# Hydrophones_0_1in_Adapter.net
KiCad netlist of a schematic drawn in Altium Designer
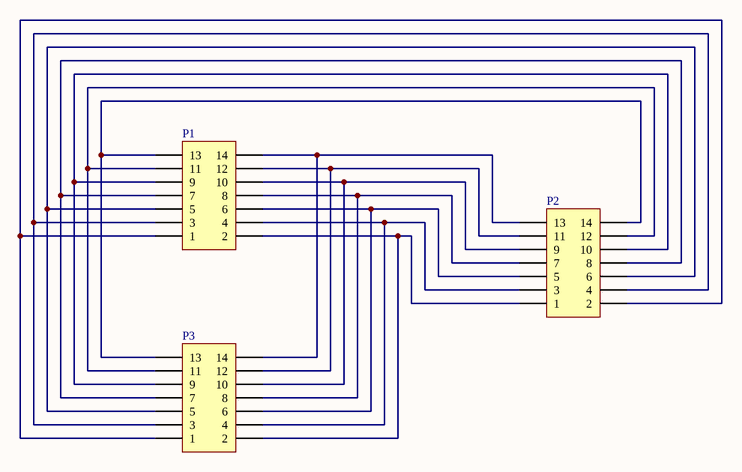
[diagram p0: Hydrophones_0.1in_Adapter.SchDoc]

(export (version "E")
  (design (tool "Eeschema 10.0.6"))
  (components
    (comp (ref "P1")
      (value "Header 7X2")
      (footprint "FTSH-107-01-F-DV")
      (description "Header, 7-Pin, Dual row")
      (fields (field (name "PUBLISHER") "Altium Limited"))
      (libsource (lib "Miscellaneous Connectors") (part "Header 7X2"))
    )
    (comp (ref "P2")
      (value "Header 7X2")
      (footprint "HDR2X7")
      (description "Header, 7-Pin, Dual row")
      (fields (field (name "PUBLISHER") "Altium Limited"))
      (libsource (lib "Miscellaneous Connectors") (part "Header 7X2"))
    )
    (comp (ref "P3")
      (value "Header 7X2")
      (footprint "FTSH-107-01-F-DV")
      (description "Header, 7-Pin, Dual row")
      (fields (field (name "PUBLISHER") "Altium Limited"))
      (libsource (lib "Miscellaneous Connectors") (part "Header 7X2"))
    )
  )
  (nets
    (net (code "1") (name "Net-(P1-Pad1)") (class "Default")
      (node (ref "P1") (pin "1") (pinfunction "1_1") (pintype "passive"))
      (node (ref "P2") (pin "2") (pinfunction "2_2") (pintype "passive"))
      (node (ref "P3") (pin "1") (pinfunction "1_1") (pintype "passive"))
    )
    (net (code "2") (name "Net-(P1-Pad2)") (class "Default")
      (node (ref "P1") (pin "2") (pinfunction "2_2") (pintype "passive"))
      (node (ref "P2") (pin "1") (pinfunction "1_1") (pintype "passive"))
      (node (ref "P3") (pin "2") (pinfunction "2_2") (pintype "passive"))
    )
    (net (code "3") (name "Net-(P1-Pad3)") (class "Default")
      (node (ref "P1") (pin "3") (pinfunction "3_3") (pintype "passive"))
      (node (ref "P2") (pin "4") (pinfunction "4_4") (pintype "passive"))
      (node (ref "P3") (pin "3") (pinfunction "3_3") (pintype "passive"))
    )
    (net (code "4") (name "Net-(P1-Pad4)") (class "Default")
      (node (ref "P1") (pin "4") (pinfunction "4_4") (pintype "passive"))
      (node (ref "P2") (pin "3") (pinfunction "3_3") (pintype "passive"))
      (node (ref "P3") (pin "4") (pinfunction "4_4") (pintype "passive"))
    )
    (net (code "5") (name "Net-(P1-Pad5)") (class "Default")
      (node (ref "P1") (pin "5") (pinfunction "5_5") (pintype "passive"))
      (node (ref "P2") (pin "6") (pinfunction "6_6") (pintype "passive"))
      (node (ref "P3") (pin "5") (pinfunction "5_5") (pintype "passive"))
    )
    (net (code "6") (name "Net-(P1-Pad6)") (class "Default")
      (node (ref "P1") (pin "6") (pinfunction "6_6") (pintype "passive"))
      (node (ref "P2") (pin "5") (pinfunction "5_5") (pintype "passive"))
      (node (ref "P3") (pin "6") (pinfunction "6_6") (pintype "passive"))
    )
    (net (code "7") (name "Net-(P1-Pad7)") (class "Default")
      (node (ref "P1") (pin "7") (pinfunction "7_7") (pintype "passive"))
      (node (ref "P2") (pin "8") (pinfunction "8_8") (pintype "passive"))
      (node (ref "P3") (pin "7") (pinfunction "7_7") (pintype "passive"))
    )
    (net (code "8") (name "Net-(P1-Pad8)") (class "Default")
      (node (ref "P1") (pin "8") (pinfunction "8_8") (pintype "passive"))
      (node (ref "P2") (pin "7") (pinfunction "7_7") (pintype "passive"))
      (node (ref "P3") (pin "8") (pinfunction "8_8") (pintype "passive"))
    )
    (net (code "9") (name "Net-(P1-Pad9)") (class "Default")
      (node (ref "P1") (pin "9") (pinfunction "9_9") (pintype "passive"))
      (node (ref "P2") (pin "10") (pinfunction "10_10") (pintype "passive"))
      (node (ref "P3") (pin "9") (pinfunction "9_9") (pintype "passive"))
    )
    (net (code "10") (name "Net-(P1-Pad10)") (class "Default")
      (node (ref "P1") (pin "10") (pinfunction "10_10") (pintype "passive"))
      (node (ref "P2") (pin "9") (pinfunction "9_9") (pintype "passive"))
      (node (ref "P3") (pin "10") (pinfunction "10_10") (pintype "passive"))
    )
    (net (code "11") (name "Net-(P1-Pad11)") (class "Default")
      (node (ref "P1") (pin "11") (pinfunction "11_11") (pintype "passive"))
      (node (ref "P2") (pin "12") (pinfunction "12_12") (pintype "passive"))
      (node (ref "P3") (pin "11") (pinfunction "11_11") (pintype "passive"))
    )
    (net (code "12") (name "Net-(P1-Pad12)") (class "Default")
      (node (ref "P1") (pin "12") (pinfunction "12_12") (pintype "passive"))
      (node (ref "P2") (pin "11") (pinfunction "11_11") (pintype "passive"))
      (node (ref "P3") (pin "12") (pinfunction "12_12") (pintype "passive"))
    )
    (net (code "13") (name "Net-(P1-Pad13)") (class "Default")
      (node (ref "P1") (pin "13") (pinfunction "13_13") (pintype "passive"))
      (node (ref "P2") (pin "14") (pinfunction "14_14") (pintype "passive"))
      (node (ref "P3") (pin "13") (pinfunction "13_13") (pintype "passive"))
    )
    (net (code "14") (name "Net-(P1-Pad14)") (class "Default")
      (node (ref "P1") (pin "14") (pinfunction "14_14") (pintype "passive"))
      (node (ref "P2") (pin "13") (pinfunction "13_13") (pintype "passive"))
      (node (ref "P3") (pin "14") (pinfunction "14_14") (pintype "passive"))
    )
  )
)
